# STM32F446_ProtoBoard.net
KiCad netlist of a schematic drawn in EAGLE
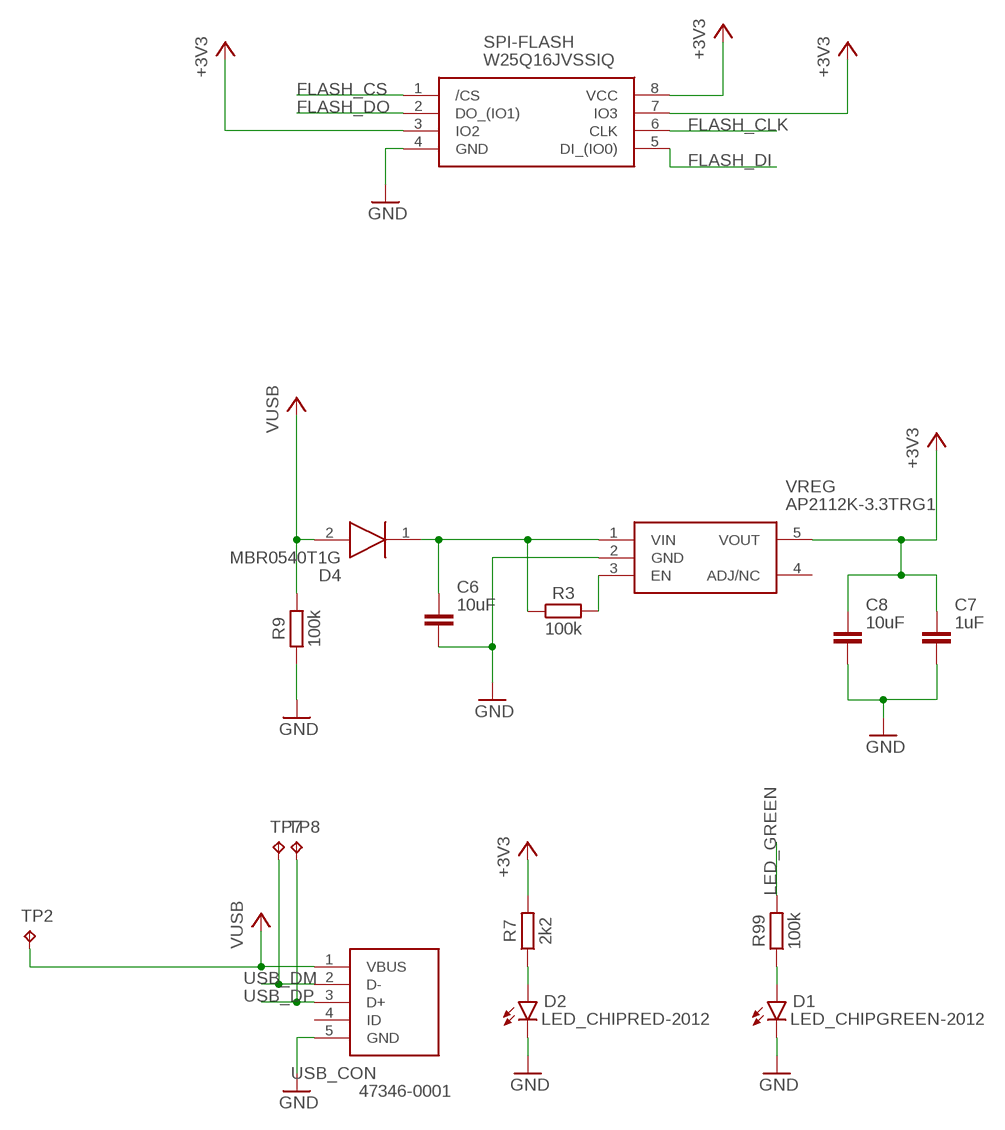
[diagram p0: schematic, sheet 1, part 1 of 2]
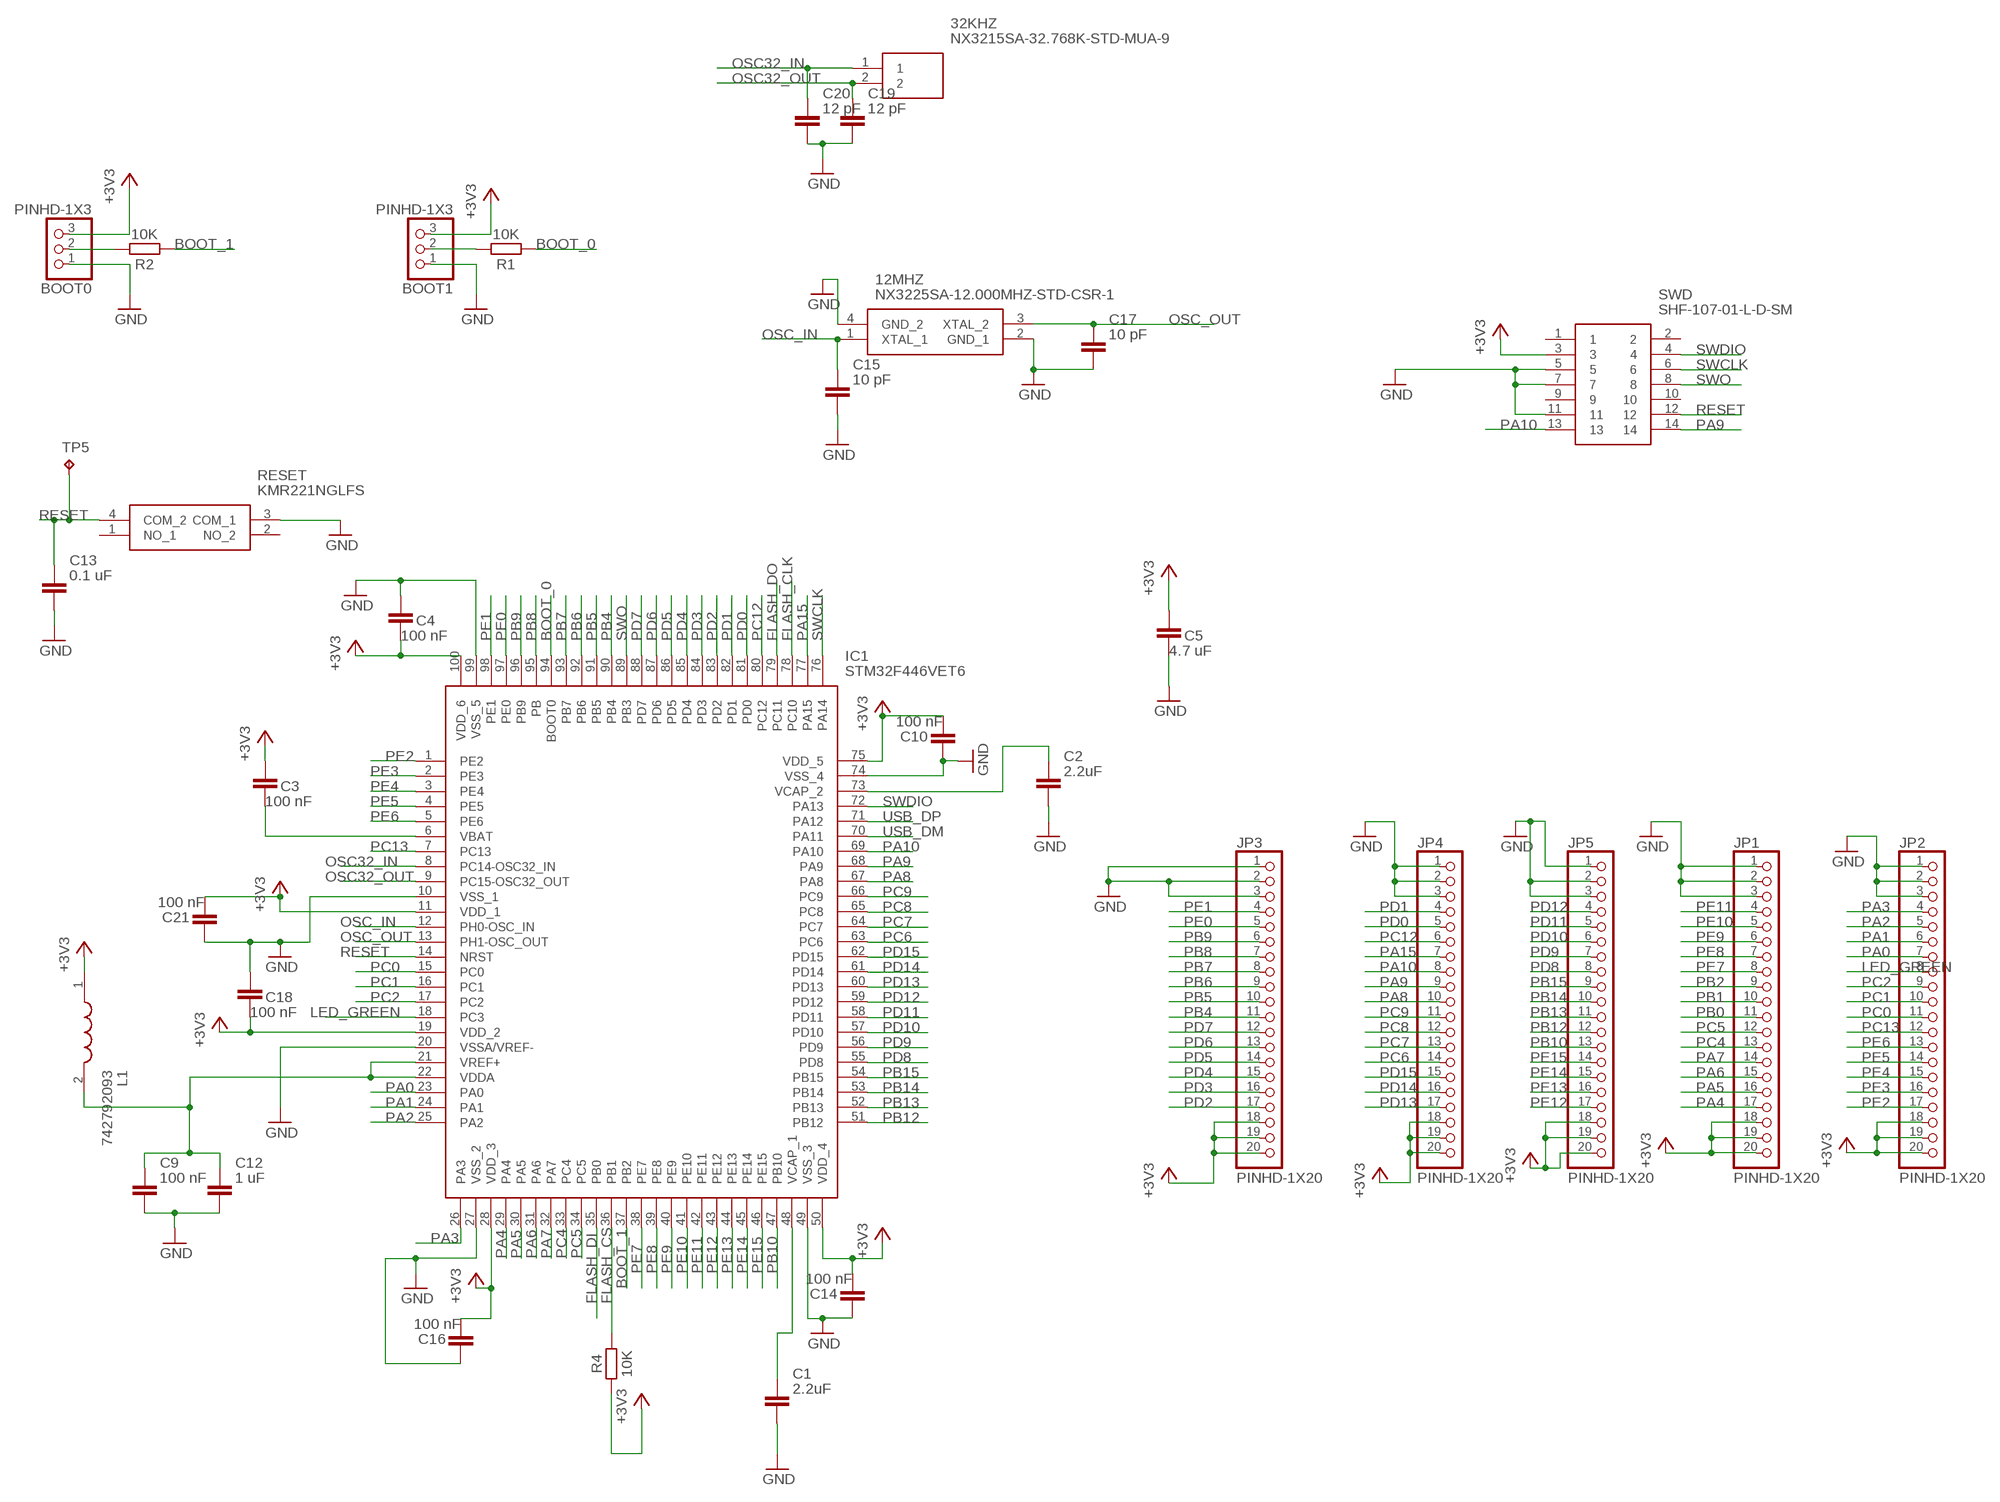
[diagram p1: schematic, sheet 1, part 2 of 2]

(export (version "E")
  (design (tool "Eeschema 10.0.6"))
  (components
    (comp (ref "12MHZ")
      (value "NX3225SA-12.000MHZ-STD-CSR-1")
      (footprint "eagle-import:NX3225SA12000MHZSTDCSR1")
      (fields (field (name "MOUSER_PART_NUMBER") "344-NX3225SA12MCSR1"))
      (libsource (lib "eagle-import") (part "NX3225SA-12.000MHZ-STD-CSR-1"))
    )
    (comp (ref "32KHZ")
      (value "NX3215SA-32.768K-STD-MUA-9")
      (footprint "eagle-import:NX3215SA")
      (fields (field (name "MOUSER_PART_NUMBER") "344-NX3215SA32768K9"))
      (libsource (lib "eagle-import") (part "NX3215SA-32.768K-STD-MUA-9"))
    )
    (comp (ref "BOOT0")
      (value "PINHD-1X3")
      (footprint "eagle-import:1X03")
      (libsource (lib "eagle-import") (part "PINHD-1X3"))
    )
    (comp (ref "BOOT1")
      (value "PINHD-1X3")
      (footprint "eagle-import:1X03")
      (libsource (lib "eagle-import") (part "PINHD-1X3"))
    )
    (comp (ref "C1")
      (value "2.2uF")
      (footprint "eagle-import:CAPC2012X110")
      (libsource (lib "eagle-import") (part "CCHIP-0805(2012-METRIC)_"))
    )
    (comp (ref "C2")
      (value "2.2uF")
      (footprint "eagle-import:CAPC2012X110")
      (libsource (lib "eagle-import") (part "CCHIP-0805(2012-METRIC)_"))
    )
    (comp (ref "C3")
      (value "100 nF")
      (footprint "eagle-import:CAPC2012X110")
      (libsource (lib "eagle-import") (part "CCHIP-0805(2012-METRIC)_"))
    )
    (comp (ref "C4")
      (value "100 nF")
      (footprint "eagle-import:CAPC2012X110")
      (libsource (lib "eagle-import") (part "CCHIP-0805(2012-METRIC)_"))
    )
    (comp (ref "C5")
      (value "4.7 uF")
      (footprint "eagle-import:CAPC2012X110")
      (libsource (lib "eagle-import") (part "CCHIP-0805(2012-METRIC)_"))
    )
    (comp (ref "C6")
      (value "10uF")
      (footprint "eagle-import:CAPC2012X110")
      (libsource (lib "eagle-import") (part "CCHIP-0805(2012-METRIC)_"))
    )
    (comp (ref "C7")
      (value "1uF")
      (footprint "eagle-import:CAPC2012X110")
      (libsource (lib "eagle-import") (part "CCHIP-0805(2012-METRIC)_"))
    )
    (comp (ref "C8")
      (value "10uF")
      (footprint "eagle-import:CAPC2012X110")
      (libsource (lib "eagle-import") (part "CCHIP-0805(2012-METRIC)_"))
    )
    (comp (ref "C9")
      (value "100 nF")
      (footprint "eagle-import:CAPC2012X110")
      (libsource (lib "eagle-import") (part "CCHIP-0805(2012-METRIC)_"))
    )
    (comp (ref "C10")
      (value "100 nF")
      (footprint "eagle-import:CAPC2012X110")
      (libsource (lib "eagle-import") (part "CCHIP-0805(2012-METRIC)_"))
    )
    (comp (ref "C12")
      (value "1 uF")
      (footprint "eagle-import:CAPC2012X110")
      (libsource (lib "eagle-import") (part "CCHIP-0805(2012-METRIC)_"))
    )
    (comp (ref "C13")
      (value "0.1 uF")
      (footprint "eagle-import:CAPC2012X110")
      (libsource (lib "eagle-import") (part "CCHIP-0805(2012-METRIC)_"))
    )
    (comp (ref "C14")
      (value "100 nF")
      (footprint "eagle-import:CAPC2012X110")
      (libsource (lib "eagle-import") (part "CCHIP-0805(2012-METRIC)_"))
    )
    (comp (ref "C15")
      (value "10 pF")
      (footprint "eagle-import:CAPC2012X110")
      (libsource (lib "eagle-import") (part "CCHIP-0805(2012-METRIC)_"))
    )
    (comp (ref "C16")
      (value "100 nF")
      (footprint "eagle-import:CAPC2012X110")
      (libsource (lib "eagle-import") (part "CCHIP-0805(2012-METRIC)_"))
    )
    (comp (ref "C17")
      (value "10 pF")
      (footprint "eagle-import:CAPC2012X110")
      (libsource (lib "eagle-import") (part "CCHIP-0805(2012-METRIC)_"))
    )
    (comp (ref "C18")
      (value "100 nF")
      (footprint "eagle-import:CAPC2012X110")
      (libsource (lib "eagle-import") (part "CCHIP-0805(2012-METRIC)_"))
    )
    (comp (ref "C19")
      (value "12 pF")
      (footprint "eagle-import:CAPC2012X110")
      (libsource (lib "eagle-import") (part "CCHIP-0805(2012-METRIC)_"))
    )
    (comp (ref "C20")
      (value "12 pF")
      (footprint "eagle-import:CAPC2012X110")
      (libsource (lib "eagle-import") (part "CCHIP-0805(2012-METRIC)_"))
    )
    (comp (ref "C21")
      (value "100 nF")
      (footprint "eagle-import:CAPC2012X110")
      (libsource (lib "eagle-import") (part "CCHIP-0805(2012-METRIC)_"))
    )
    (comp (ref "D1")
      (value "LED_CHIPGREEN-2012")
      (footprint "eagle-import:LEDC2012X110N_G")
      (libsource (lib "eagle-import") (part "LED_CHIPGREEN-2012"))
    )
    (comp (ref "D2")
      (value "LED_CHIPRED-2012")
      (footprint "eagle-import:LEDC2012X110N_R")
      (libsource (lib "eagle-import") (part "LED_CHIPRED-2012"))
    )
    (comp (ref "D4")
      (value "MBR0540T1G")
      (footprint "eagle-import:SOD3716X135N")
      (fields (field (name "MOUSER_PART_NUMBER") "863-MBR0540T1G"))
      (libsource (lib "eagle-import") (part "MBR0540T1G"))
    )
    (comp (ref "IC1")
      (value "STM32F446VET6")
      (footprint "eagle-import:QFP50P1600X1600X160-100N")
      (fields (field (name "MOUSER_PART_NUMBER") "511-STM32F446VET6"))
      (libsource (lib "eagle-import") (part "STM32F446VET6"))
    )
    (comp (ref "JP1")
      (value "PINHD-1X20")
      (footprint "eagle-import:1X20")
      (libsource (lib "eagle-import") (part "PINHD-1X20"))
    )
    (comp (ref "JP2")
      (value "PINHD-1X20")
      (footprint "eagle-import:1X20")
      (libsource (lib "eagle-import") (part "PINHD-1X20"))
    )
    (comp (ref "JP3")
      (value "PINHD-1X20")
      (footprint "eagle-import:1X20")
      (libsource (lib "eagle-import") (part "PINHD-1X20"))
    )
    (comp (ref "JP4")
      (value "PINHD-1X20")
      (footprint "eagle-import:1X20")
      (libsource (lib "eagle-import") (part "PINHD-1X20"))
    )
    (comp (ref "JP5")
      (value "PINHD-1X20")
      (footprint "eagle-import:1X20")
      (libsource (lib "eagle-import") (part "PINHD-1X20"))
    )
    (comp (ref "L1")
      (value "742792093")
      (footprint "eagle-import:CAPC2012X110N")
      (fields (field (name "MOUSER_PART_NUMBER") "710-742792093"))
      (libsource (lib "eagle-import") (part "742792093"))
    )
    (comp (ref "R1")
      (value "10K")
      (footprint "eagle-import:RESC2012X65")
      (libsource (lib "eagle-import") (part "RCHIP-0805(2012-METRIC)_"))
    )
    (comp (ref "R2")
      (value "10K")
      (footprint "eagle-import:RESC2012X65")
      (libsource (lib "eagle-import") (part "RCHIP-0805(2012-METRIC)_"))
    )
    (comp (ref "R3")
      (value "100k")
      (footprint "eagle-import:RESC2012X65")
      (libsource (lib "eagle-import") (part "RCHIP-0805(2012-METRIC)_"))
    )
    (comp (ref "R4")
      (value "10K")
      (footprint "eagle-import:RESC2012X65")
      (libsource (lib "eagle-import") (part "RCHIP-0805(2012-METRIC)_"))
    )
    (comp (ref "R7")
      (value "2k2")
      (footprint "eagle-import:RESC2012X65")
      (libsource (lib "eagle-import") (part "RCHIP-0805(2012-METRIC)_"))
    )
    (comp (ref "R9")
      (value "100k")
      (footprint "eagle-import:RESC2012X65")
      (libsource (lib "eagle-import") (part "RCHIP-0805(2012-METRIC)_"))
    )
    (comp (ref "R99")
      (value "100k")
      (footprint "eagle-import:RESC2012X65")
      (libsource (lib "eagle-import") (part "RCHIP-0805(2012-METRIC)_"))
    )
    (comp (ref "RESET")
      (value "KMR221NGLFS")
      (footprint "eagle-import:KMR221NGLFS")
      (fields (field (name "MOUSER_PART_NUMBER") "611-KMR221NGLFS"))
      (libsource (lib "eagle-import") (part "KMR221NGLFS"))
    )
    (comp (ref "SPI-FLASH")
      (value "W25Q16JVSSIQ")
      (footprint "eagle-import:SOIC127P790X216-8N")
      (fields (field (name "MOUSER_PART_NUMBER") "454-W25Q16JVSSIQ"))
      (libsource (lib "eagle-import") (part "W25Q16JVSSIQ"))
    )
    (comp (ref "SWD")
      (value "SHF-107-01-L-D-SM")
      (footprint "eagle-import:SHF-107-01-X-D-SM")
      (fields (field (name "MOUSER_PART_NUMBER") "200-SHF10701LDSM"))
      (libsource (lib "eagle-import") (part "SHF-107-01-L-D-SM"))
    )
    (comp (ref "TP2")
      (value "TPTP20R")
      (footprint "eagle-import:TP20R")
      (libsource (lib "eagle-import") (part "TPTP20R"))
    )
    (comp (ref "TP5")
      (value "TPTP20R")
      (footprint "eagle-import:TP20R")
      (libsource (lib "eagle-import") (part "TPTP20R"))
    )
    (comp (ref "TP7")
      (value "TPTP20R")
      (footprint "eagle-import:TP20R")
      (libsource (lib "eagle-import") (part "TPTP20R"))
    )
    (comp (ref "TP8")
      (value "TPTP20R")
      (footprint "eagle-import:TP20R")
      (libsource (lib "eagle-import") (part "TPTP20R"))
    )
    (comp (ref "USB_CON")
      (value "47346-0001")
      (footprint "eagle-import:47346-0001")
      (fields (field (name "MOUSER_PART_NUMBER") "538-47346-0001"))
      (libsource (lib "eagle-import") (part "47346-0001"))
    )
    (comp (ref "VREG")
      (value "AP2112K-3.3TRG1")
      (footprint "eagle-import:SOT95P282X130-5N")
      (fields (field (name "MOUSER_PART_NUMBER") "621-AP2112K-3.3TRG1"))
      (libsource (lib "eagle-import") (part "AP2112K-3.3TRG1"))
    )
  )
  (nets
    (net (code "1") (name "+3V3") (class "Default")
      (node (ref "BOOT0") (pin "3") (pinfunction "3_3") (pintype "passive"))
      (node (ref "BOOT1") (pin "3") (pinfunction "3_3") (pintype "passive"))
      (node (ref "C10") (pin "2") (pinfunction "2_2") (pintype "passive"))
      (node (ref "C14") (pin "2") (pinfunction "2_2") (pintype "passive"))
      (node (ref "C16") (pin "2") (pinfunction "2_2") (pintype "passive"))
      (node (ref "C18") (pin "2") (pinfunction "2_2") (pintype "passive"))
      (node (ref "C21") (pin "2") (pinfunction "2_2") (pintype "passive"))
      (node (ref "C3") (pin "1") (pinfunction "1_1") (pintype "passive"))
      (node (ref "C4") (pin "2") (pinfunction "2_2") (pintype "passive"))
      (node (ref "C5") (pin "1") (pinfunction "1_1") (pintype "passive"))
      (node (ref "C7") (pin "1") (pinfunction "1_1") (pintype "passive"))
      (node (ref "C8") (pin "1") (pinfunction "1_1") (pintype "passive"))
      (node (ref "IC1") (pin "100") (pinfunction "VDD_6_100") (pintype "bidirectional"))
      (node (ref "IC1") (pin "11") (pinfunction "VDD_1_11") (pintype "bidirectional"))
      (node (ref "IC1") (pin "19") (pinfunction "VDD_2_19") (pintype "bidirectional"))
      (node (ref "IC1") (pin "28") (pinfunction "VDD_3_28") (pintype "bidirectional"))
      (node (ref "IC1") (pin "50") (pinfunction "VDD_4_50") (pintype "bidirectional"))
      (node (ref "IC1") (pin "75") (pinfunction "VDD_5_75") (pintype "bidirectional"))
      (node (ref "JP1") (pin "18") (pinfunction "18_18") (pintype "passive"))
      (node (ref "JP1") (pin "19") (pinfunction "19_19") (pintype "passive"))
      (node (ref "JP1") (pin "20") (pinfunction "20_20") (pintype "passive"))
      (node (ref "JP2") (pin "18") (pinfunction "18_18") (pintype "passive"))
      (node (ref "JP2") (pin "19") (pinfunction "19_19") (pintype "passive"))
      (node (ref "JP2") (pin "20") (pinfunction "20_20") (pintype "passive"))
      (node (ref "JP3") (pin "18") (pinfunction "18_18") (pintype "passive"))
      (node (ref "JP3") (pin "19") (pinfunction "19_19") (pintype "passive"))
      (node (ref "JP3") (pin "20") (pinfunction "20_20") (pintype "passive"))
      (node (ref "JP4") (pin "18") (pinfunction "18_18") (pintype "passive"))
      (node (ref "JP4") (pin "19") (pinfunction "19_19") (pintype "passive"))
      (node (ref "JP4") (pin "20") (pinfunction "20_20") (pintype "passive"))
      (node (ref "JP5") (pin "18") (pinfunction "18_18") (pintype "passive"))
      (node (ref "JP5") (pin "19") (pinfunction "19_19") (pintype "passive"))
      (node (ref "JP5") (pin "20") (pinfunction "20_20") (pintype "passive"))
      (node (ref "L1") (pin "1") (pinfunction "1_1") (pintype "bidirectional"))
      (node (ref "R4") (pin "1") (pinfunction "1_1") (pintype "passive"))
      (node (ref "R7") (pin "2") (pinfunction "2_2") (pintype "passive"))
      (node (ref "SPI-FLASH") (pin "3") (pinfunction "IO2_3") (pintype "bidirectional"))
      (node (ref "SPI-FLASH") (pin "7") (pinfunction "IO3_7") (pintype "bidirectional"))
      (node (ref "SPI-FLASH") (pin "8") (pinfunction "VCC_8") (pintype "bidirectional"))
      (node (ref "SWD") (pin "3") (pinfunction "3_3") (pintype "bidirectional"))
      (node (ref "VREG") (pin "5") (pinfunction "VOUT_5") (pintype "bidirectional"))
    )
    (net (code "2") (name "/BOOT_0") (class "Default")
      (node (ref "IC1") (pin "94") (pinfunction "BOOT0_94") (pintype "bidirectional"))
      (node (ref "R1") (pin "1") (pinfunction "1_1") (pintype "passive"))
    )
    (net (code "3") (name "/BOOT_1") (class "Default")
      (node (ref "IC1") (pin "37") (pinfunction "PB2_37") (pintype "bidirectional"))
      (node (ref "R2") (pin "1") (pinfunction "1_1") (pintype "passive"))
    )
    (net (code "4") (name "/FLASH_CLK") (class "Default")
      (node (ref "IC1") (pin "78") (pinfunction "PC10_78") (pintype "bidirectional"))
      (node (ref "SPI-FLASH") (pin "6") (pinfunction "CLK_6") (pintype "bidirectional"))
    )
    (net (code "5") (name "/FLASH_CS") (class "Default")
      (node (ref "IC1") (pin "36") (pinfunction "PB1_36") (pintype "bidirectional"))
      (node (ref "R4") (pin "2") (pinfunction "2_2") (pintype "passive"))
      (node (ref "SPI-FLASH") (pin "1") (pinfunction "/CS_1") (pintype "bidirectional"))
    )
    (net (code "6") (name "/FLASH_DI") (class "Default")
      (node (ref "IC1") (pin "35") (pinfunction "PB0_35") (pintype "bidirectional"))
      (node (ref "SPI-FLASH") (pin "5") (pinfunction "DI_(IO0)_5") (pintype "bidirectional"))
    )
    (net (code "7") (name "/FLASH_DO") (class "Default")
      (node (ref "IC1") (pin "79") (pinfunction "PC11_79") (pintype "bidirectional"))
      (node (ref "SPI-FLASH") (pin "2") (pinfunction "DO_(IO1)_2") (pintype "bidirectional"))
    )
    (net (code "8") (name "/LED_GREEN") (class "Default")
      (node (ref "IC1") (pin "18") (pinfunction "PC3_18") (pintype "bidirectional"))
      (node (ref "JP2") (pin "8") (pinfunction "8_8") (pintype "passive"))
      (node (ref "R99") (pin "2") (pinfunction "2_2") (pintype "passive"))
    )
    (net (code "9") (name "/OSC32_IN") (class "Default")
      (node (ref "32KHZ") (pin "1") (pinfunction "1_1") (pintype "bidirectional"))
      (node (ref "C20") (pin "1") (pinfunction "1_1") (pintype "passive"))
      (node (ref "IC1") (pin "8") (pinfunction "PC14-OSC32_IN_8") (pintype "bidirectional"))
    )
    (net (code "10") (name "/OSC32_OUT") (class "Default")
      (node (ref "32KHZ") (pin "2") (pinfunction "2_2") (pintype "bidirectional"))
      (node (ref "C19") (pin "1") (pinfunction "1_1") (pintype "passive"))
      (node (ref "IC1") (pin "9") (pinfunction "PC15-OSC32_OUT_9") (pintype "bidirectional"))
    )
    (net (code "11") (name "/OSC_IN") (class "Default")
      (node (ref "12MHZ") (pin "1") (pinfunction "XTAL_1_1") (pintype "bidirectional"))
      (node (ref "C15") (pin "1") (pinfunction "1_1") (pintype "passive"))
      (node (ref "IC1") (pin "12") (pinfunction "PH0-OSC_IN_12") (pintype "bidirectional"))
    )
    (net (code "12") (name "/OSC_OUT") (class "Default")
      (node (ref "12MHZ") (pin "3") (pinfunction "XTAL_2_3") (pintype "bidirectional"))
      (node (ref "C17") (pin "1") (pinfunction "1_1") (pintype "passive"))
      (node (ref "IC1") (pin "13") (pinfunction "PH1-OSC_OUT_13") (pintype "bidirectional"))
    )
    (net (code "13") (name "/PA0") (class "Default")
      (node (ref "IC1") (pin "23") (pinfunction "PA0_23") (pintype "bidirectional"))
      (node (ref "JP2") (pin "7") (pinfunction "7_7") (pintype "passive"))
    )
    (net (code "14") (name "/PA1") (class "Default")
      (node (ref "IC1") (pin "24") (pinfunction "PA1_24") (pintype "bidirectional"))
      (node (ref "JP2") (pin "6") (pinfunction "6_6") (pintype "passive"))
    )
    (net (code "15") (name "/PA2") (class "Default")
      (node (ref "IC1") (pin "25") (pinfunction "PA2_25") (pintype "bidirectional"))
      (node (ref "JP2") (pin "5") (pinfunction "5_5") (pintype "passive"))
    )
    (net (code "16") (name "/PA3") (class "Default")
      (node (ref "IC1") (pin "26") (pinfunction "PA3_26") (pintype "bidirectional"))
      (node (ref "JP2") (pin "4") (pinfunction "4_4") (pintype "passive"))
    )
    (net (code "17") (name "/PA4") (class "Default")
      (node (ref "IC1") (pin "29") (pinfunction "PA4_29") (pintype "bidirectional"))
      (node (ref "JP1") (pin "17") (pinfunction "17_17") (pintype "passive"))
    )
    (net (code "18") (name "/PA5") (class "Default")
      (node (ref "IC1") (pin "30") (pinfunction "PA5_30") (pintype "bidirectional"))
      (node (ref "JP1") (pin "16") (pinfunction "16_16") (pintype "passive"))
    )
    (net (code "19") (name "/PA6") (class "Default")
      (node (ref "IC1") (pin "31") (pinfunction "PA6_31") (pintype "bidirectional"))
      (node (ref "JP1") (pin "15") (pinfunction "15_15") (pintype "passive"))
    )
    (net (code "20") (name "/PA7") (class "Default")
      (node (ref "IC1") (pin "32") (pinfunction "PA7_32") (pintype "bidirectional"))
      (node (ref "JP1") (pin "14") (pinfunction "14_14") (pintype "passive"))
    )
    (net (code "21") (name "/PA8") (class "Default")
      (node (ref "IC1") (pin "67") (pinfunction "PA8_67") (pintype "bidirectional"))
      (node (ref "JP4") (pin "10") (pinfunction "10_10") (pintype "passive"))
    )
    (net (code "22") (name "/PA9") (class "Default")
      (node (ref "IC1") (pin "68") (pinfunction "PA9_68") (pintype "bidirectional"))
      (node (ref "JP4") (pin "9") (pinfunction "9_9") (pintype "passive"))
      (node (ref "SWD") (pin "14") (pinfunction "14_14") (pintype "bidirectional"))
    )
    (net (code "23") (name "/PA10") (class "Default")
      (node (ref "IC1") (pin "69") (pinfunction "PA10_69") (pintype "bidirectional"))
      (node (ref "JP4") (pin "8") (pinfunction "8_8") (pintype "passive"))
      (node (ref "SWD") (pin "13") (pinfunction "13_13") (pintype "bidirectional"))
    )
    (net (code "24") (name "/PA15") (class "Default")
      (node (ref "IC1") (pin "77") (pinfunction "PA15_77") (pintype "bidirectional"))
      (node (ref "JP4") (pin "7") (pinfunction "7_7") (pintype "passive"))
    )
    (net (code "25") (name "/PB0") (class "Default")
      (node (ref "JP1") (pin "11") (pinfunction "11_11") (pintype "passive"))
    )
    (net (code "26") (name "/PB1") (class "Default")
      (node (ref "JP1") (pin "10") (pinfunction "10_10") (pintype "passive"))
    )
    (net (code "27") (name "/PB2") (class "Default")
      (node (ref "JP1") (pin "9") (pinfunction "9_9") (pintype "passive"))
    )
    (net (code "28") (name "/PB4") (class "Default")
      (node (ref "IC1") (pin "90") (pinfunction "PB4_90") (pintype "bidirectional"))
      (node (ref "JP3") (pin "11") (pinfunction "11_11") (pintype "passive"))
    )
    (net (code "29") (name "/PB5") (class "Default")
      (node (ref "IC1") (pin "91") (pinfunction "PB5_91") (pintype "bidirectional"))
      (node (ref "JP3") (pin "10") (pinfunction "10_10") (pintype "passive"))
    )
    (net (code "30") (name "/PB6") (class "Default")
      (node (ref "IC1") (pin "92") (pinfunction "PB6_92") (pintype "bidirectional"))
      (node (ref "JP3") (pin "9") (pinfunction "9_9") (pintype "passive"))
    )
    (net (code "31") (name "/PB7") (class "Default")
      (node (ref "IC1") (pin "93") (pinfunction "PB7_93") (pintype "bidirectional"))
      (node (ref "JP3") (pin "8") (pinfunction "8_8") (pintype "passive"))
    )
    (net (code "32") (name "/PB8") (class "Default")
      (node (ref "IC1") (pin "95") (pinfunction "PB_95") (pintype "bidirectional"))
      (node (ref "JP3") (pin "7") (pinfunction "7_7") (pintype "passive"))
    )
    (net (code "33") (name "/PB9") (class "Default")
      (node (ref "IC1") (pin "96") (pinfunction "PB9_96") (pintype "bidirectional"))
      (node (ref "JP3") (pin "6") (pinfunction "6_6") (pintype "passive"))
    )
    (net (code "34") (name "/PB10") (class "Default")
      (node (ref "IC1") (pin "47") (pinfunction "PB10_47") (pintype "bidirectional"))
      (node (ref "JP5") (pin "13") (pinfunction "13_13") (pintype "passive"))
    )
    (net (code "35") (name "/PB12") (class "Default")
      (node (ref "IC1") (pin "51") (pinfunction "PB12_51") (pintype "bidirectional"))
      (node (ref "JP5") (pin "12") (pinfunction "12_12") (pintype "passive"))
    )
    (net (code "36") (name "/PB13") (class "Default")
      (node (ref "IC1") (pin "52") (pinfunction "PB13_52") (pintype "bidirectional"))
      (node (ref "JP5") (pin "11") (pinfunction "11_11") (pintype "passive"))
    )
    (net (code "37") (name "/PB14") (class "Default")
      (node (ref "IC1") (pin "53") (pinfunction "PB14_53") (pintype "bidirectional"))
      (node (ref "JP5") (pin "10") (pinfunction "10_10") (pintype "passive"))
    )
    (net (code "38") (name "/PB15") (class "Default")
      (node (ref "IC1") (pin "54") (pinfunction "PB15_54") (pintype "bidirectional"))
      (node (ref "JP5") (pin "9") (pinfunction "9_9") (pintype "passive"))
    )
    (net (code "39") (name "/PC0") (class "Default")
      (node (ref "IC1") (pin "15") (pinfunction "PC0_15") (pintype "bidirectional"))
      (node (ref "JP2") (pin "11") (pinfunction "11_11") (pintype "passive"))
    )
    (net (code "40") (name "/PC1") (class "Default")
      (node (ref "IC1") (pin "16") (pinfunction "PC1_16") (pintype "bidirectional"))
      (node (ref "JP2") (pin "10") (pinfunction "10_10") (pintype "passive"))
    )
    (net (code "41") (name "/PC2") (class "Default")
      (node (ref "IC1") (pin "17") (pinfunction "PC2_17") (pintype "bidirectional"))
      (node (ref "JP2") (pin "9") (pinfunction "9_9") (pintype "passive"))
    )
    (net (code "42") (name "/PC4") (class "Default")
      (node (ref "IC1") (pin "33") (pinfunction "PC4_33") (pintype "bidirectional"))
      (node (ref "JP1") (pin "13") (pinfunction "13_13") (pintype "passive"))
    )
    (net (code "43") (name "/PC5") (class "Default")
      (node (ref "IC1") (pin "34") (pinfunction "PC5_34") (pintype "bidirectional"))
      (node (ref "JP1") (pin "12") (pinfunction "12_12") (pintype "passive"))
    )
    (net (code "44") (name "/PC6") (class "Default")
      (node (ref "IC1") (pin "63") (pinfunction "PC6_63") (pintype "bidirectional"))
      (node (ref "JP4") (pin "14") (pinfunction "14_14") (pintype "passive"))
    )
    (net (code "45") (name "/PC7") (class "Default")
      (node (ref "IC1") (pin "64") (pinfunction "PC7_64") (pintype "bidirectional"))
      (node (ref "JP4") (pin "13") (pinfunction "13_13") (pintype "passive"))
    )
    (net (code "46") (name "/PC8") (class "Default")
      (node (ref "IC1") (pin "65") (pinfunction "PC8_65") (pintype "bidirectional"))
      (node (ref "JP4") (pin "12") (pinfunction "12_12") (pintype "passive"))
    )
    (net (code "47") (name "/PC9") (class "Default")
      (node (ref "IC1") (pin "66") (pinfunction "PC9_66") (pintype "bidirectional"))
      (node (ref "JP4") (pin "11") (pinfunction "11_11") (pintype "passive"))
    )
    (net (code "48") (name "/PC12") (class "Default")
      (node (ref "IC1") (pin "80") (pinfunction "PC12_80") (pintype "bidirectional"))
      (node (ref "JP4") (pin "6") (pinfunction "6_6") (pintype "passive"))
    )
    (net (code "49") (name "/PC13") (class "Default")
      (node (ref "IC1") (pin "7") (pinfunction "PC13_7") (pintype "bidirectional"))
      (node (ref "JP2") (pin "12") (pinfunction "12_12") (pintype "passive"))
    )
    (net (code "50") (name "/PD0") (class "Default")
      (node (ref "IC1") (pin "81") (pinfunction "PD0_81") (pintype "bidirectional"))
      (node (ref "JP4") (pin "5") (pinfunction "5_5") (pintype "passive"))
    )
    (net (code "51") (name "/PD1") (class "Default")
      (node (ref "IC1") (pin "82") (pinfunction "PD1_82") (pintype "bidirectional"))
      (node (ref "JP4") (pin "4") (pinfunction "4_4") (pintype "passive"))
    )
    (net (code "52") (name "/PD2") (class "Default")
      (node (ref "IC1") (pin "83") (pinfunction "PD2_83") (pintype "bidirectional"))
      (node (ref "JP3") (pin "17") (pinfunction "17_17") (pintype "passive"))
    )
    (net (code "53") (name "/PD3") (class "Default")
      (node (ref "IC1") (pin "84") (pinfunction "PD3_84") (pintype "bidirectional"))
      (node (ref "JP3") (pin "16") (pinfunction "16_16") (pintype "passive"))
    )
    (net (code "54") (name "/PD4") (class "Default")
      (node (ref "IC1") (pin "85") (pinfunction "PD4_85") (pintype "bidirectional"))
      (node (ref "JP3") (pin "15") (pinfunction "15_15") (pintype "passive"))
    )
    (net (code "55") (name "/PD5") (class "Default")
      (node (ref "IC1") (pin "86") (pinfunction "PD5_86") (pintype "bidirectional"))
      (node (ref "JP3") (pin "14") (pinfunction "14_14") (pintype "passive"))
    )
    (net (code "56") (name "/PD6") (class "Default")
      (node (ref "IC1") (pin "87") (pinfunction "PD6_87") (pintype "bidirectional"))
      (node (ref "JP3") (pin "13") (pinfunction "13_13") (pintype "passive"))
    )
    (net (code "57") (name "/PD7") (class "Default")
      (node (ref "IC1") (pin "88") (pinfunction "PD7_88") (pintype "bidirectional"))
      (node (ref "JP3") (pin "12") (pinfunction "12_12") (pintype "passive"))
    )
    (net (code "58") (name "/PD8") (class "Default")
      (node (ref "IC1") (pin "55") (pinfunction "PD8_55") (pintype "bidirectional"))
      (node (ref "JP5") (pin "8") (pinfunction "8_8") (pintype "passive"))
    )
    (net (code "59") (name "/PD9") (class "Default")
      (node (ref "IC1") (pin "56") (pinfunction "PD9_56") (pintype "bidirectional"))
      (node (ref "JP5") (pin "7") (pinfunction "7_7") (pintype "passive"))
    )
    (net (code "60") (name "/PD10") (class "Default")
      (node (ref "IC1") (pin "57") (pinfunction "PD10_57") (pintype "bidirectional"))
      (node (ref "JP5") (pin "6") (pinfunction "6_6") (pintype "passive"))
    )
    (net (code "61") (name "/PD11") (class "Default")
      (node (ref "IC1") (pin "58") (pinfunction "PD11_58") (pintype "bidirectional"))
      (node (ref "JP5") (pin "5") (pinfunction "5_5") (pintype "passive"))
    )
    (net (code "62") (name "/PD12") (class "Default")
      (node (ref "IC1") (pin "59") (pinfunction "PD12_59") (pintype "bidirectional"))
      (node (ref "JP5") (pin "4") (pinfunction "4_4") (pintype "passive"))
    )
    (net (code "63") (name "/PD13") (class "Default")
      (node (ref "IC1") (pin "60") (pinfunction "PD13_60") (pintype "bidirectional"))
      (node (ref "JP4") (pin "17") (pinfunction "17_17") (pintype "passive"))
    )
    (net (code "64") (name "/PD14") (class "Default")
      (node (ref "IC1") (pin "61") (pinfunction "PD14_61") (pintype "bidirectional"))
      (node (ref "JP4") (pin "16") (pinfunction "16_16") (pintype "passive"))
    )
    (net (code "65") (name "/PD15") (class "Default")
      (node (ref "IC1") (pin "62") (pinfunction "PD15_62") (pintype "bidirectional"))
      (node (ref "JP4") (pin "15") (pinfunction "15_15") (pintype "passive"))
    )
    (net (code "66") (name "/PE0") (class "Default")
      (node (ref "IC1") (pin "97") (pinfunction "PE0_97") (pintype "bidirectional"))
      (node (ref "JP3") (pin "5") (pinfunction "5_5") (pintype "passive"))
    )
    (net (code "67") (name "/PE1") (class "Default")
      (node (ref "IC1") (pin "98") (pinfunction "PE1_98") (pintype "bidirectional"))
      (node (ref "JP3") (pin "4") (pinfunction "4_4") (pintype "passive"))
    )
    (net (code "68") (name "/PE2") (class "Default")
      (node (ref "IC1") (pin "1") (pinfunction "PE2_1") (pintype "bidirectional"))
      (node (ref "JP2") (pin "17") (pinfunction "17_17") (pintype "passive"))
    )
    (net (code "69") (name "/PE3") (class "Default")
      (node (ref "IC1") (pin "2") (pinfunction "PE3_2") (pintype "bidirectional"))
      (node (ref "JP2") (pin "16") (pinfunction "16_16") (pintype "passive"))
    )
    (net (code "70") (name "/PE4") (class "Default")
      (node (ref "IC1") (pin "3") (pinfunction "PE4_3") (pintype "bidirectional"))
      (node (ref "JP2") (pin "15") (pinfunction "15_15") (pintype "passive"))
    )
    (net (code "71") (name "/PE5") (class "Default")
      (node (ref "IC1") (pin "4") (pinfunction "PE5_4") (pintype "bidirectional"))
      (node (ref "JP2") (pin "14") (pinfunction "14_14") (pintype "passive"))
    )
    (net (code "72") (name "/PE6") (class "Default")
      (node (ref "IC1") (pin "5") (pinfunction "PE6_5") (pintype "bidirectional"))
      (node (ref "JP2") (pin "13") (pinfunction "13_13") (pintype "passive"))
    )
    (net (code "73") (name "/PE7") (class "Default")
      (node (ref "IC1") (pin "38") (pinfunction "PE7_38") (pintype "bidirectional"))
      (node (ref "JP1") (pin "8") (pinfunction "8_8") (pintype "passive"))
    )
    (net (code "74") (name "/PE8") (class "Default")
      (node (ref "IC1") (pin "39") (pinfunction "PE8_39") (pintype "bidirectional"))
      (node (ref "JP1") (pin "7") (pinfunction "7_7") (pintype "passive"))
    )
    (net (code "75") (name "/PE9") (class "Default")
      (node (ref "IC1") (pin "40") (pinfunction "PE9_40") (pintype "bidirectional"))
      (node (ref "JP1") (pin "6") (pinfunction "6_6") (pintype "passive"))
    )
    (net (code "76") (name "/PE10") (class "Default")
      (node (ref "IC1") (pin "41") (pinfunction "PE10_41") (pintype "bidirectional"))
      (node (ref "JP1") (pin "5") (pinfunction "5_5") (pintype "passive"))
    )
    (net (code "77") (name "/PE11") (class "Default")
      (node (ref "IC1") (pin "42") (pinfunction "PE11_42") (pintype "bidirectional"))
      (node (ref "JP1") (pin "4") (pinfunction "4_4") (pintype "passive"))
    )
    (net (code "78") (name "/PE12") (class "Default")
      (node (ref "IC1") (pin "43") (pinfunction "PE12_43") (pintype "bidirectional"))
      (node (ref "JP5") (pin "17") (pinfunction "17_17") (pintype "passive"))
    )
    (net (code "79") (name "/PE13") (class "Default")
      (node (ref "IC1") (pin "44") (pinfunction "PE13_44") (pintype "bidirectional"))
      (node (ref "JP5") (pin "16") (pinfunction "16_16") (pintype "passive"))
    )
    (net (code "80") (name "/PE14") (class "Default")
      (node (ref "IC1") (pin "45") (pinfunction "PE14_45") (pintype "bidirectional"))
      (node (ref "JP5") (pin "15") (pinfunction "15_15") (pintype "passive"))
    )
    (net (code "81") (name "/PE15") (class "Default")
      (node (ref "IC1") (pin "46") (pinfunction "PE15_46") (pintype "bidirectional"))
      (node (ref "JP5") (pin "14") (pinfunction "14_14") (pintype "passive"))
    )
    (net (code "82") (name "/RESET") (class "Default")
      (node (ref "C13") (pin "1") (pinfunction "1_1") (pintype "passive"))
      (node (ref "IC1") (pin "14") (pinfunction "NRST_14") (pintype "bidirectional"))
      (node (ref "RESET") (pin "4") (pinfunction "COM_2_4") (pintype "bidirectional"))
      (node (ref "SWD") (pin "12") (pinfunction "12_12") (pintype "bidirectional"))
      (node (ref "TP5") (pin "TP") (pinfunction "TP_TP") (pintype "input"))
    )
    (net (code "83") (name "/SWCLK") (class "Default")
      (node (ref "IC1") (pin "76") (pinfunction "PA14_76") (pintype "bidirectional"))
      (node (ref "SWD") (pin "6") (pinfunction "6_6") (pintype "bidirectional"))
    )
    (net (code "84") (name "/SWDIO") (class "Default")
      (node (ref "IC1") (pin "72") (pinfunction "PA13_72") (pintype "bidirectional"))
      (node (ref "SWD") (pin "4") (pinfunction "4_4") (pintype "bidirectional"))
    )
    (net (code "85") (name "/SWO") (class "Default")
      (node (ref "IC1") (pin "89") (pinfunction "PB3_89") (pintype "bidirectional"))
      (node (ref "SWD") (pin "8") (pinfunction "8_8") (pintype "bidirectional"))
    )
    (net (code "86") (name "/USB_DM") (class "Default")
      (node (ref "IC1") (pin "70") (pinfunction "PA11_70") (pintype "bidirectional"))
      (node (ref "TP7") (pin "TP") (pinfunction "TP_TP") (pintype "input"))
      (node (ref "USB_CON") (pin "2") (pinfunction "D-_2") (pintype "bidirectional"))
    )
    (net (code "87") (name "/USB_DP") (class "Default")
      (node (ref "IC1") (pin "71") (pinfunction "PA12_71") (pintype "bidirectional"))
      (node (ref "TP8") (pin "TP") (pinfunction "TP_TP") (pintype "input"))
      (node (ref "USB_CON") (pin "3") (pinfunction "D+_3") (pintype "bidirectional"))
    )
    (net (code "88") (name "GND") (class "Default")
      (node (ref "12MHZ") (pin "2") (pinfunction "GND_1_2") (pintype "bidirectional"))
      (node (ref "12MHZ") (pin "4") (pinfunction "GND_2_4") (pintype "bidirectional"))
      (node (ref "BOOT0") (pin "1") (pinfunction "1_1") (pintype "passive"))
      (node (ref "BOOT1") (pin "1") (pinfunction "1_1") (pintype "passive"))
      (node (ref "C1") (pin "2") (pinfunction "2_2") (pintype "passive"))
      (node (ref "C10") (pin "1") (pinfunction "1_1") (pintype "passive"))
      (node (ref "C12") (pin "2") (pinfunction "2_2") (pintype "passive"))
      (node (ref "C13") (pin "2") (pinfunction "2_2") (pintype "passive"))
      (node (ref "C14") (pin "1") (pinfunction "1_1") (pintype "passive"))
      (node (ref "C15") (pin "2") (pinfunction "2_2") (pintype "passive"))
      (node (ref "C16") (pin "1") (pinfunction "1_1") (pintype "passive"))
      (node (ref "C17") (pin "2") (pinfunction "2_2") (pintype "passive"))
      (node (ref "C18") (pin "1") (pinfunction "1_1") (pintype "passive"))
      (node (ref "C19") (pin "2") (pinfunction "2_2") (pintype "passive"))
      (node (ref "C2") (pin "2") (pinfunction "2_2") (pintype "passive"))
      (node (ref "C20") (pin "2") (pinfunction "2_2") (pintype "passive"))
      (node (ref "C21") (pin "1") (pinfunction "1_1") (pintype "passive"))
      (node (ref "C4") (pin "1") (pinfunction "1_1") (pintype "passive"))
      (node (ref "C5") (pin "2") (pinfunction "2_2") (pintype "passive"))
      (node (ref "C6") (pin "2") (pinfunction "2_2") (pintype "passive"))
      (node (ref "C7") (pin "2") (pinfunction "2_2") (pintype "passive"))
      (node (ref "C8") (pin "2") (pinfunction "2_2") (pintype "passive"))
      (node (ref "C9") (pin "2") (pinfunction "2_2") (pintype "passive"))
      (node (ref "D1") (pin "1") (pinfunction "C_1") (pintype "passive"))
      (node (ref "D2") (pin "1") (pinfunction "C_1") (pintype "passive"))
      (node (ref "IC1") (pin "10") (pinfunction "VSS_1_10") (pintype "bidirectional"))
      (node (ref "IC1") (pin "20") (pinfunction "VSSA/VREF-_20") (pintype "bidirectional"))
      (node (ref "IC1") (pin "27") (pinfunction "VSS_2_27") (pintype "bidirectional"))
      (node (ref "IC1") (pin "49") (pinfunction "VSS_3_49") (pintype "bidirectional"))
      (node (ref "IC1") (pin "74") (pinfunction "VSS_4_74") (pintype "bidirectional"))
      (node (ref "IC1") (pin "99") (pinfunction "VSS_5_99") (pintype "bidirectional"))
      (node (ref "JP1") (pin "1") (pinfunction "1_1") (pintype "passive"))
      (node (ref "JP1") (pin "2") (pinfunction "2_2") (pintype "passive"))
      (node (ref "JP1") (pin "3") (pinfunction "3_3") (pintype "passive"))
      (node (ref "JP2") (pin "1") (pinfunction "1_1") (pintype "passive"))
      (node (ref "JP2") (pin "2") (pinfunction "2_2") (pintype "passive"))
      (node (ref "JP2") (pin "3") (pinfunction "3_3") (pintype "passive"))
      (node (ref "JP3") (pin "1") (pinfunction "1_1") (pintype "passive"))
      (node (ref "JP3") (pin "2") (pinfunction "2_2") (pintype "passive"))
      (node (ref "JP3") (pin "3") (pinfunction "3_3") (pintype "passive"))
      (node (ref "JP4") (pin "1") (pinfunction "1_1") (pintype "passive"))
      (node (ref "JP4") (pin "2") (pinfunction "2_2") (pintype "passive"))
      (node (ref "JP4") (pin "3") (pinfunction "3_3") (pintype "passive"))
      (node (ref "JP5") (pin "1") (pinfunction "1_1") (pintype "passive"))
      (node (ref "JP5") (pin "2") (pinfunction "2_2") (pintype "passive"))
      (node (ref "JP5") (pin "3") (pinfunction "3_3") (pintype "passive"))
      (node (ref "R9") (pin "1") (pinfunction "1_1") (pintype "passive"))
      (node (ref "RESET") (pin "3") (pinfunction "COM_1_3") (pintype "bidirectional"))
      (node (ref "SPI-FLASH") (pin "4") (pinfunction "GND_4") (pintype "bidirectional"))
      (node (ref "SWD") (pin "11") (pinfunction "11_11") (pintype "bidirectional"))
      (node (ref "SWD") (pin "5") (pinfunction "5_5") (pintype "bidirectional"))
      (node (ref "SWD") (pin "7") (pinfunction "7_7") (pintype "bidirectional"))
      (node (ref "USB_CON") (pin "5") (pinfunction "GND_5") (pintype "bidirectional"))
      (node (ref "VREG") (pin "2") (pinfunction "GND_2") (pintype "bidirectional"))
    )
    (net (code "89") (name "Net-(BOOT0-Pad2)") (class "Default")
      (node (ref "BOOT0") (pin "2") (pinfunction "2_2") (pintype "passive"))
      (node (ref "R2") (pin "2") (pinfunction "2_2") (pintype "passive"))
    )
    (net (code "90") (name "Net-(BOOT1-Pad2)") (class "Default")
      (node (ref "BOOT1") (pin "2") (pinfunction "2_2") (pintype "passive"))
      (node (ref "R1") (pin "2") (pinfunction "2_2") (pintype "passive"))
    )
    (net (code "91") (name "Net-(D1-A)") (class "Default")
      (node (ref "D1") (pin "2") (pinfunction "A_2") (pintype "passive"))
      (node (ref "R99") (pin "1") (pinfunction "1_1") (pintype "passive"))
    )
    (net (code "92") (name "Net-(D2-A)") (class "Default")
      (node (ref "D2") (pin "2") (pinfunction "A_2") (pintype "passive"))
      (node (ref "R7") (pin "1") (pinfunction "1_1") (pintype "passive"))
    )
    (net (code "93") (name "Net-(D4-K)") (class "Default")
      (node (ref "C6") (pin "1") (pinfunction "1_1") (pintype "passive"))
      (node (ref "D4") (pin "1") (pinfunction "K_1") (pintype "bidirectional"))
      (node (ref "R3") (pin "1") (pinfunction "1_1") (pintype "passive"))
      (node (ref "VREG") (pin "1") (pinfunction "VIN_1") (pintype "bidirectional"))
    )
    (net (code "94") (name "Net-(IC1-VBAT)") (class "Default")
      (node (ref "C3") (pin "2") (pinfunction "2_2") (pintype "passive"))
      (node (ref "IC1") (pin "6") (pinfunction "VBAT_6") (pintype "bidirectional"))
    )
    (net (code "95") (name "Net-(IC1-VCAP_1)") (class "Default")
      (node (ref "C1") (pin "1") (pinfunction "1_1") (pintype "passive"))
      (node (ref "IC1") (pin "48") (pinfunction "VCAP_1_48") (pintype "bidirectional"))
    )
    (net (code "96") (name "Net-(IC1-VCAP_2)") (class "Default")
      (node (ref "C2") (pin "1") (pinfunction "1_1") (pintype "passive"))
      (node (ref "IC1") (pin "73") (pinfunction "VCAP_2_73") (pintype "bidirectional"))
    )
    (net (code "97") (name "Net-(IC1-VDDA)") (class "Default")
      (node (ref "C12") (pin "1") (pinfunction "1_1") (pintype "passive"))
      (node (ref "C9") (pin "1") (pinfunction "1_1") (pintype "passive"))
      (node (ref "IC1") (pin "21") (pinfunction "VREF+_21") (pintype "bidirectional"))
      (node (ref "IC1") (pin "22") (pinfunction "VDDA_22") (pintype "bidirectional"))
      (node (ref "L1") (pin "2") (pinfunction "2_2") (pintype "bidirectional"))
    )
    (net (code "98") (name "Net-(VREG-EN)") (class "Default")
      (node (ref "R3") (pin "2") (pinfunction "2_2") (pintype "passive"))
      (node (ref "VREG") (pin "3") (pinfunction "EN_3") (pintype "bidirectional"))
    )
    (net (code "99") (name "VUSB") (class "Default")
      (node (ref "D4") (pin "2") (pinfunction "A_2") (pintype "bidirectional"))
      (node (ref "R9") (pin "2") (pinfunction "2_2") (pintype "passive"))
      (node (ref "TP2") (pin "TP") (pinfunction "TP_TP") (pintype "input"))
      (node (ref "USB_CON") (pin "1") (pinfunction "VBUS_1") (pintype "bidirectional"))
    )
    (net (code "100") (name "unconnected-(RESET-NO_1-Pad1)") (class "Default")
      (node (ref "RESET") (pin "1") (pinfunction "NO_1_1") (pintype "bidirectional"))
    )
    (net (code "101") (name "unconnected-(RESET-NO_2-Pad2)") (class "Default")
      (node (ref "RESET") (pin "2") (pinfunction "NO_2_2") (pintype "bidirectional"))
    )
    (net (code "102") (name "unconnected-(SWD-Pad1)") (class "Default")
      (node (ref "SWD") (pin "1") (pinfunction "1_1") (pintype "bidirectional"))
    )
    (net (code "103") (name "unconnected-(SWD-Pad2)") (class "Default")
      (node (ref "SWD") (pin "2") (pinfunction "2_2") (pintype "bidirectional"))
    )
    (net (code "104") (name "unconnected-(SWD-Pad9)") (class "Default")
      (node (ref "SWD") (pin "9") (pinfunction "9_9") (pintype "bidirectional"))
    )
    (net (code "105") (name "unconnected-(SWD-Pad10)") (class "Default")
      (node (ref "SWD") (pin "10") (pinfunction "10_10") (pintype "bidirectional"))
    )
    (net (code "106") (name "unconnected-(USB_CON-ID-Pad4)") (class "Default")
      (node (ref "USB_CON") (pin "4") (pinfunction "ID_4") (pintype "bidirectional"))
    )
    (net (code "107") (name "unconnected-(VREG-ADJ{slash}NC-Pad4)") (class "Default")
      (node (ref "VREG") (pin "4") (pinfunction "ADJ/NC_4") (pintype "bidirectional"))
    )
  )
)
